# working.net
KiCad netlist of a schematic drawn in EAGLE
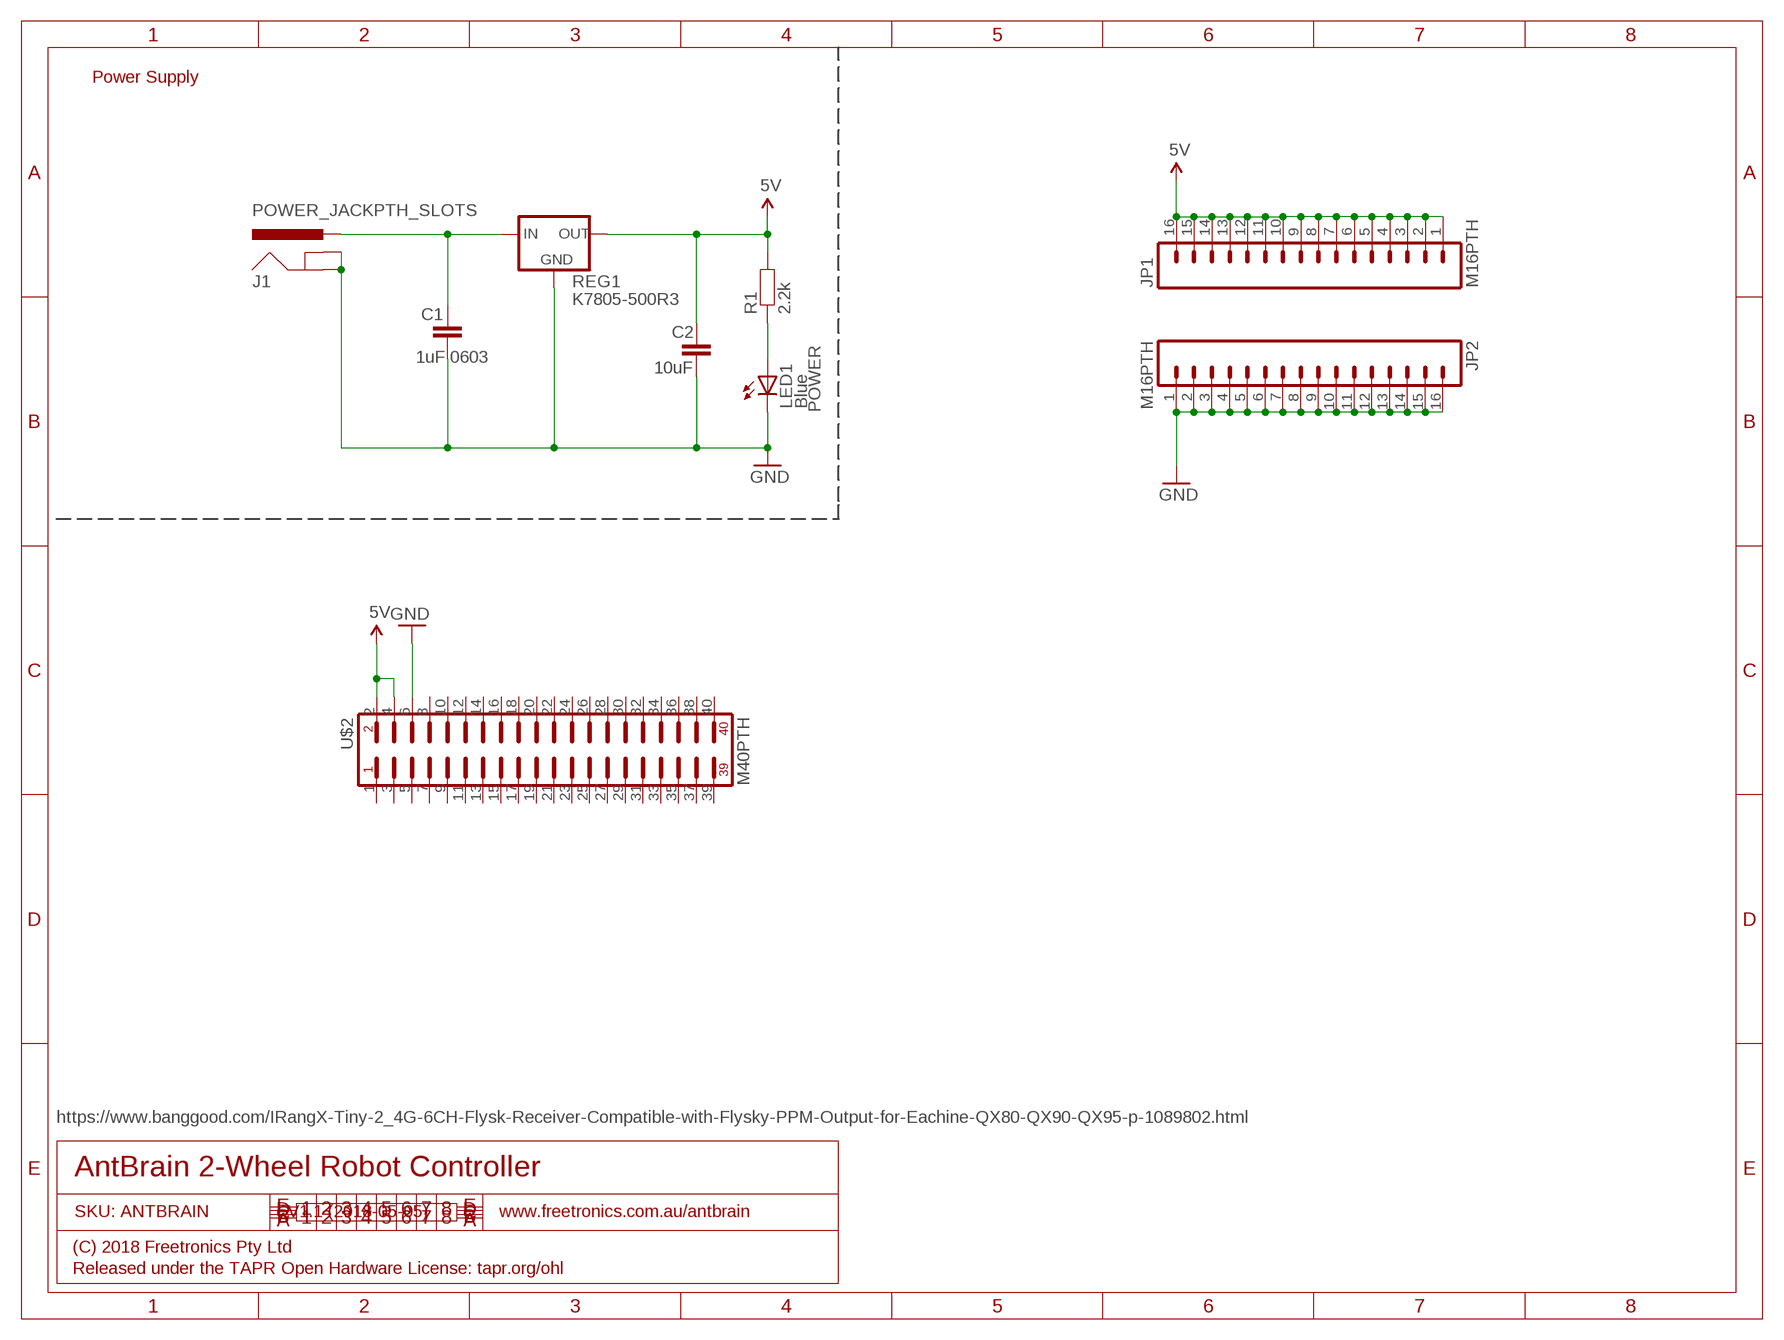
[diagram p0: schematic, sheet 1]

(export (version "E")
  (design (tool "Eeschema 10.0.6"))
  (components
    (comp (ref "C1")
      (value "1uF 0603")
      (footprint "eagle-import:0603")
      (libsource (lib "eagle-import") (part "CAP0603"))
    )
    (comp (ref "C2")
      (value "10uF")
      (footprint "eagle-import:0805")
      (libsource (lib "eagle-import") (part "freetronics-jon_CAP0805"))
    )
    (comp (ref "J1")
      (value "POWER_JACKPTH_SLOTS")
      (footprint "eagle-import:POWER_JACK_PTH_SLOTS")
      (libsource (lib "eagle-import") (part "POWER_JACKPTH_SLOTS"))
    )
    (comp (ref "JP1")
      (value "M16PTH")
      (footprint "eagle-import:1X16")
      (libsource (lib "eagle-import") (part "M16PTH"))
    )
    (comp (ref "JP2")
      (value "M16PTH")
      (footprint "eagle-import:1X16")
      (libsource (lib "eagle-import") (part "M16PTH"))
    )
    (comp (ref "LED1")
      (value "Blue")
      (footprint "eagle-import:LED-0603")
      (libsource (lib "eagle-import") (part "LED0603"))
    )
    (comp (ref "R1")
      (value "2.2k")
      (footprint "eagle-import:0603")
      (libsource (lib "eagle-import") (part "RESISTOR0603"))
    )
    (comp (ref "REG1")
      (value "K7805-500R3")
      (footprint "eagle-import:K78XX-500R3")
      (libsource (lib "eagle-import") (part "K78XX-500R3"))
    )
    (comp (ref "U$2")
      (value "M40PTH")
      (footprint "eagle-import:2X20")
      (libsource (lib "eagle-import") (part "M40PTH"))
    )
  )
  (nets
    (net (code "1") (name "5V") (class "Default")
      (node (ref "C2") (pin "1") (pinfunction "1_1") (pintype "passive"))
      (node (ref "JP1") (pin "1") (pinfunction "1_1") (pintype "passive"))
      (node (ref "JP1") (pin "10") (pinfunction "10_10") (pintype "passive"))
      (node (ref "JP1") (pin "11") (pinfunction "11_11") (pintype "passive"))
      (node (ref "JP1") (pin "12") (pinfunction "12_12") (pintype "passive"))
      (node (ref "JP1") (pin "13") (pinfunction "13_13") (pintype "passive"))
      (node (ref "JP1") (pin "14") (pinfunction "14_14") (pintype "passive"))
      (node (ref "JP1") (pin "15") (pinfunction "15_15") (pintype "passive"))
      (node (ref "JP1") (pin "16") (pinfunction "16_16") (pintype "passive"))
      (node (ref "JP1") (pin "2") (pinfunction "2_2") (pintype "passive"))
      (node (ref "JP1") (pin "3") (pinfunction "3_3") (pintype "passive"))
      (node (ref "JP1") (pin "4") (pinfunction "4_4") (pintype "passive"))
      (node (ref "JP1") (pin "5") (pinfunction "5_5") (pintype "passive"))
      (node (ref "JP1") (pin "6") (pinfunction "6_6") (pintype "passive"))
      (node (ref "JP1") (pin "7") (pinfunction "7_7") (pintype "passive"))
      (node (ref "JP1") (pin "8") (pinfunction "8_8") (pintype "passive"))
      (node (ref "JP1") (pin "9") (pinfunction "9_9") (pintype "passive"))
      (node (ref "R1") (pin "2") (pinfunction "2_2") (pintype "passive"))
      (node (ref "REG1") (pin "3") (pinfunction "OUT_3") (pintype "output"))
      (node (ref "U$2") (pin "2") (pinfunction "2_2") (pintype "passive"))
      (node (ref "U$2") (pin "4") (pinfunction "4_4") (pintype "passive"))
    )
    (net (code "2") (name "GND") (class "Default")
      (node (ref "C1") (pin "2") (pinfunction "2_2") (pintype "passive"))
      (node (ref "C2") (pin "2") (pinfunction "2_2") (pintype "passive"))
      (node (ref "J1") (pin "GND") (pinfunction "GND_GND") (pintype "bidirectional"))
      (node (ref "J1") (pin "GNDBREAK") (pinfunction "GNDBREAK_GNDBREAK") (pintype "bidirectional"))
      (node (ref "JP2") (pin "1") (pinfunction "1_1") (pintype "passive"))
      (node (ref "JP2") (pin "10") (pinfunction "10_10") (pintype "passive"))
      (node (ref "JP2") (pin "11") (pinfunction "11_11") (pintype "passive"))
      (node (ref "JP2") (pin "12") (pinfunction "12_12") (pintype "passive"))
      (node (ref "JP2") (pin "13") (pinfunction "13_13") (pintype "passive"))
      (node (ref "JP2") (pin "14") (pinfunction "14_14") (pintype "passive"))
      (node (ref "JP2") (pin "15") (pinfunction "15_15") (pintype "passive"))
      (node (ref "JP2") (pin "16") (pinfunction "16_16") (pintype "passive"))
      (node (ref "JP2") (pin "2") (pinfunction "2_2") (pintype "passive"))
      (node (ref "JP2") (pin "3") (pinfunction "3_3") (pintype "passive"))
      (node (ref "JP2") (pin "4") (pinfunction "4_4") (pintype "passive"))
      (node (ref "JP2") (pin "5") (pinfunction "5_5") (pintype "passive"))
      (node (ref "JP2") (pin "6") (pinfunction "6_6") (pintype "passive"))
      (node (ref "JP2") (pin "7") (pinfunction "7_7") (pintype "passive"))
      (node (ref "JP2") (pin "8") (pinfunction "8_8") (pintype "passive"))
      (node (ref "JP2") (pin "9") (pinfunction "9_9") (pintype "passive"))
      (node (ref "LED1") (pin "C") (pinfunction "C_C") (pintype "passive"))
      (node (ref "REG1") (pin "2") (pinfunction "GND_2") (pintype "input"))
      (node (ref "U$2") (pin "6") (pinfunction "6_6") (pintype "passive"))
    )
    (net (code "3") (name "Net-(LED1-PadA)") (class "Default")
      (node (ref "LED1") (pin "A") (pinfunction "A_A") (pintype "passive"))
      (node (ref "R1") (pin "1") (pinfunction "1_1") (pintype "passive"))
    )
    (net (code "4") (name "Net-(REG1-IN)") (class "Default")
      (node (ref "C1") (pin "1") (pinfunction "1_1") (pintype "passive"))
      (node (ref "J1") (pin "PWR") (pinfunction "PWR_PWR") (pintype "bidirectional"))
      (node (ref "REG1") (pin "1") (pinfunction "IN_1") (pintype "input"))
    )
    (net (code "5") (name "unconnected-(U$2-Pad1)") (class "Default")
      (node (ref "U$2") (pin "1") (pinfunction "1_1") (pintype "passive"))
    )
    (net (code "6") (name "unconnected-(U$2-Pad3)") (class "Default")
      (node (ref "U$2") (pin "3") (pinfunction "3_3") (pintype "passive"))
    )
    (net (code "7") (name "unconnected-(U$2-Pad5)") (class "Default")
      (node (ref "U$2") (pin "5") (pinfunction "5_5") (pintype "passive"))
    )
    (net (code "8") (name "unconnected-(U$2-Pad7)") (class "Default")
      (node (ref "U$2") (pin "7") (pinfunction "7_7") (pintype "passive"))
    )
    (net (code "9") (name "unconnected-(U$2-Pad8)") (class "Default")
      (node (ref "U$2") (pin "8") (pinfunction "8_8") (pintype "passive"))
    )
    (net (code "10") (name "unconnected-(U$2-Pad9)") (class "Default")
      (node (ref "U$2") (pin "9") (pinfunction "9_9") (pintype "passive"))
    )
    (net (code "11") (name "unconnected-(U$2-Pad10)") (class "Default")
      (node (ref "U$2") (pin "10") (pinfunction "10_10") (pintype "passive"))
    )
    (net (code "12") (name "unconnected-(U$2-Pad11)") (class "Default")
      (node (ref "U$2") (pin "11") (pinfunction "11_11") (pintype "passive"))
    )
    (net (code "13") (name "unconnected-(U$2-Pad12)") (class "Default")
      (node (ref "U$2") (pin "12") (pinfunction "12_12") (pintype "passive"))
    )
    (net (code "14") (name "unconnected-(U$2-Pad13)") (class "Default")
      (node (ref "U$2") (pin "13") (pinfunction "13_13") (pintype "passive"))
    )
    (net (code "15") (name "unconnected-(U$2-Pad14)") (class "Default")
      (node (ref "U$2") (pin "14") (pinfunction "14_14") (pintype "passive"))
    )
    (net (code "16") (name "unconnected-(U$2-Pad15)") (class "Default")
      (node (ref "U$2") (pin "15") (pinfunction "15_15") (pintype "passive"))
    )
    (net (code "17") (name "unconnected-(U$2-Pad16)") (class "Default")
      (node (ref "U$2") (pin "16") (pinfunction "16_16") (pintype "passive"))
    )
    (net (code "18") (name "unconnected-(U$2-Pad17)") (class "Default")
      (node (ref "U$2") (pin "17") (pinfunction "17_17") (pintype "passive"))
    )
    (net (code "19") (name "unconnected-(U$2-Pad18)") (class "Default")
      (node (ref "U$2") (pin "18") (pinfunction "18_18") (pintype "passive"))
    )
    (net (code "20") (name "unconnected-(U$2-Pad19)") (class "Default")
      (node (ref "U$2") (pin "19") (pinfunction "19_19") (pintype "passive"))
    )
    (net (code "21") (name "unconnected-(U$2-Pad20)") (class "Default")
      (node (ref "U$2") (pin "20") (pinfunction "20_20") (pintype "passive"))
    )
    (net (code "22") (name "unconnected-(U$2-Pad21)") (class "Default")
      (node (ref "U$2") (pin "21") (pinfunction "21_21") (pintype "passive"))
    )
    (net (code "23") (name "unconnected-(U$2-Pad22)") (class "Default")
      (node (ref "U$2") (pin "22") (pinfunction "22_22") (pintype "passive"))
    )
    (net (code "24") (name "unconnected-(U$2-Pad23)") (class "Default")
      (node (ref "U$2") (pin "23") (pinfunction "23_23") (pintype "passive"))
    )
    (net (code "25") (name "unconnected-(U$2-Pad24)") (class "Default")
      (node (ref "U$2") (pin "24") (pinfunction "24_24") (pintype "passive"))
    )
    (net (code "26") (name "unconnected-(U$2-Pad25)") (class "Default")
      (node (ref "U$2") (pin "25") (pinfunction "25_25") (pintype "passive"))
    )
    (net (code "27") (name "unconnected-(U$2-Pad26)") (class "Default")
      (node (ref "U$2") (pin "26") (pinfunction "26_26") (pintype "passive"))
    )
    (net (code "28") (name "unconnected-(U$2-Pad27)") (class "Default")
      (node (ref "U$2") (pin "27") (pinfunction "27_27") (pintype "passive"))
    )
    (net (code "29") (name "unconnected-(U$2-Pad28)") (class "Default")
      (node (ref "U$2") (pin "28") (pinfunction "28_28") (pintype "passive"))
    )
    (net (code "30") (name "unconnected-(U$2-Pad29)") (class "Default")
      (node (ref "U$2") (pin "29") (pinfunction "29_29") (pintype "passive"))
    )
    (net (code "31") (name "unconnected-(U$2-Pad30)") (class "Default")
      (node (ref "U$2") (pin "30") (pinfunction "30_30") (pintype "passive"))
    )
    (net (code "32") (name "unconnected-(U$2-Pad31)") (class "Default")
      (node (ref "U$2") (pin "31") (pinfunction "31_31") (pintype "passive"))
    )
    (net (code "33") (name "unconnected-(U$2-Pad32)") (class "Default")
      (node (ref "U$2") (pin "32") (pinfunction "32_32") (pintype "passive"))
    )
    (net (code "34") (name "unconnected-(U$2-Pad33)") (class "Default")
      (node (ref "U$2") (pin "33") (pinfunction "33_33") (pintype "passive"))
    )
    (net (code "35") (name "unconnected-(U$2-Pad34)") (class "Default")
      (node (ref "U$2") (pin "34") (pinfunction "34_34") (pintype "passive"))
    )
    (net (code "36") (name "unconnected-(U$2-Pad35)") (class "Default")
      (node (ref "U$2") (pin "35") (pinfunction "35_35") (pintype "passive"))
    )
    (net (code "37") (name "unconnected-(U$2-Pad36)") (class "Default")
      (node (ref "U$2") (pin "36") (pinfunction "36_36") (pintype "passive"))
    )
    (net (code "38") (name "unconnected-(U$2-Pad37)") (class "Default")
      (node (ref "U$2") (pin "37") (pinfunction "37_37") (pintype "passive"))
    )
    (net (code "39") (name "unconnected-(U$2-Pad38)") (class "Default")
      (node (ref "U$2") (pin "38") (pinfunction "38_38") (pintype "passive"))
    )
    (net (code "40") (name "unconnected-(U$2-Pad39)") (class "Default")
      (node (ref "U$2") (pin "39") (pinfunction "39_39") (pintype "passive"))
    )
    (net (code "41") (name "unconnected-(U$2-Pad40)") (class "Default")
      (node (ref "U$2") (pin "40") (pinfunction "40_40") (pintype "passive"))
    )
  )
)
